# Mainboard_MotorDriverInterface.net
KiCad netlist of a schematic drawn in Altium Designer
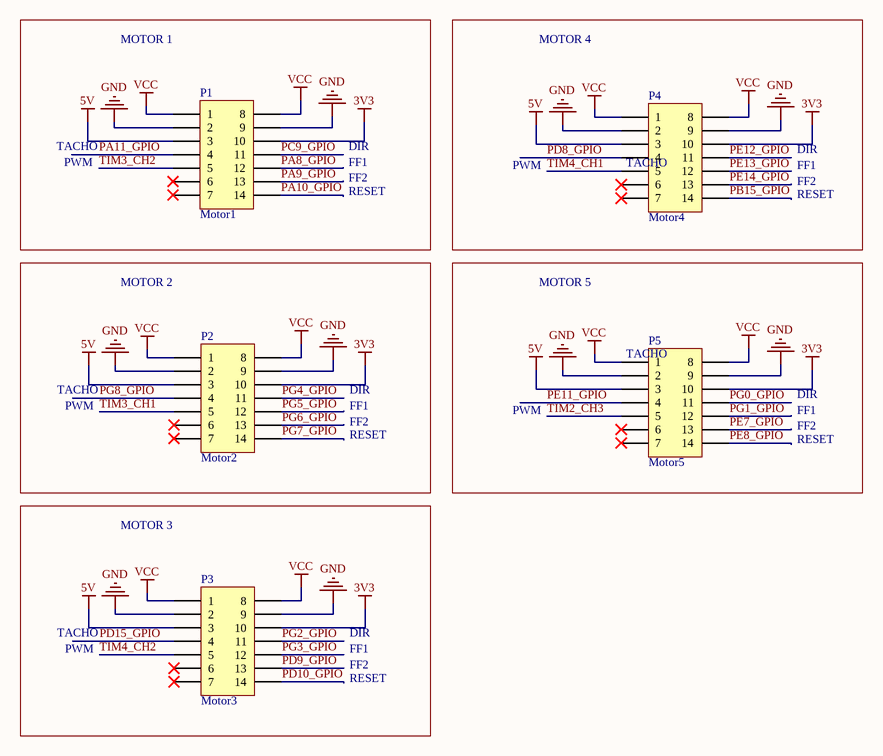
[diagram p0: Mainboard_MotorDriverInterface.SchDoc]

(export (version "E")
  (design (tool "Eeschema 10.0.6"))
  (components
    (comp (ref "P1")
      (value "Motor1")
      (footprint "HDR2X7_CEN")
      (description "Header, 7-Pin, Dual row")
      (fields (field (name "PUBLISHER") "Altium Limited"))
      (libsource (lib "Miscellaneous Connectors") (part "Header 7X2A"))
    )
    (comp (ref "P2")
      (value "Motor2")
      (footprint "HDR2X7_CEN")
      (description "Header, 7-Pin, Dual row")
      (fields (field (name "PUBLISHER") "Altium Limited"))
      (libsource (lib "Miscellaneous Connectors") (part "Header 7X2A"))
    )
    (comp (ref "P3")
      (value "Motor3")
      (footprint "HDR2X7_CEN")
      (description "Header, 7-Pin, Dual row")
      (fields (field (name "PUBLISHER") "Altium Limited"))
      (libsource (lib "Miscellaneous Connectors") (part "Header 7X2A"))
    )
    (comp (ref "P4")
      (value "Motor4")
      (footprint "HDR2X7_CEN")
      (description "Header, 7-Pin, Dual row")
      (fields (field (name "PUBLISHER") "Altium Limited"))
      (libsource (lib "Miscellaneous Connectors") (part "Header 7X2A"))
    )
    (comp (ref "P5")
      (value "Motor5")
      (footprint "HDR2X7_CEN")
      (description "Header, 7-Pin, Dual row")
      (fields (field (name "PUBLISHER") "Altium Limited"))
      (libsource (lib "Miscellaneous Connectors") (part "Header 7X2A"))
    )
  )
  (nets
    (net (code "1") (name "/PA8_GPIO") (class "Default")
      (node (ref "P1") (pin "12") (pinfunction "12_12") (pintype "passive"))
    )
    (net (code "2") (name "/PA9_GPIO") (class "Default")
      (node (ref "P1") (pin "13") (pinfunction "13_13") (pintype "passive"))
    )
    (net (code "3") (name "/PA10_GPIO") (class "Default")
      (node (ref "P1") (pin "14") (pinfunction "14_14") (pintype "passive"))
    )
    (net (code "4") (name "/PA11_GPIO") (class "Default")
      (node (ref "P1") (pin "4") (pinfunction "4_4") (pintype "passive"))
    )
    (net (code "5") (name "/PB15_GPIO") (class "Default")
      (node (ref "P4") (pin "14") (pinfunction "14_14") (pintype "passive"))
    )
    (net (code "6") (name "/PC9_GPIO") (class "Default")
      (node (ref "P1") (pin "11") (pinfunction "11_11") (pintype "passive"))
    )
    (net (code "7") (name "/PD8_GPIO") (class "Default")
      (node (ref "P4") (pin "4") (pinfunction "4_4") (pintype "passive"))
    )
    (net (code "8") (name "/PD9_GPIO") (class "Default")
      (node (ref "P3") (pin "13") (pinfunction "13_13") (pintype "passive"))
    )
    (net (code "9") (name "/PD10_GPIO") (class "Default")
      (node (ref "P3") (pin "14") (pinfunction "14_14") (pintype "passive"))
    )
    (net (code "10") (name "/PD15_GPIO") (class "Default")
      (node (ref "P3") (pin "4") (pinfunction "4_4") (pintype "passive"))
    )
    (net (code "11") (name "/PE7_GPIO") (class "Default")
      (node (ref "P5") (pin "13") (pinfunction "13_13") (pintype "passive"))
    )
    (net (code "12") (name "/PE8_GPIO") (class "Default")
      (node (ref "P5") (pin "14") (pinfunction "14_14") (pintype "passive"))
    )
    (net (code "13") (name "/PE11_GPIO") (class "Default")
      (node (ref "P5") (pin "4") (pinfunction "4_4") (pintype "passive"))
    )
    (net (code "14") (name "/PE12_GPIO") (class "Default")
      (node (ref "P4") (pin "11") (pinfunction "11_11") (pintype "passive"))
    )
    (net (code "15") (name "/PE13_GPIO") (class "Default")
      (node (ref "P4") (pin "12") (pinfunction "12_12") (pintype "passive"))
    )
    (net (code "16") (name "/PE14_GPIO") (class "Default")
      (node (ref "P4") (pin "13") (pinfunction "13_13") (pintype "passive"))
    )
    (net (code "17") (name "/PG0_GPIO") (class "Default")
      (node (ref "P5") (pin "11") (pinfunction "11_11") (pintype "passive"))
    )
    (net (code "18") (name "/PG1_GPIO") (class "Default")
      (node (ref "P5") (pin "12") (pinfunction "12_12") (pintype "passive"))
    )
    (net (code "19") (name "/PG2_GPIO") (class "Default")
      (node (ref "P3") (pin "11") (pinfunction "11_11") (pintype "passive"))
    )
    (net (code "20") (name "/PG3_GPIO") (class "Default")
      (node (ref "P3") (pin "12") (pinfunction "12_12") (pintype "passive"))
    )
    (net (code "21") (name "/PG4_GPIO") (class "Default")
      (node (ref "P2") (pin "11") (pinfunction "11_11") (pintype "passive"))
    )
    (net (code "22") (name "/PG5_GPIO") (class "Default")
      (node (ref "P2") (pin "12") (pinfunction "12_12") (pintype "passive"))
    )
    (net (code "23") (name "/PG6_GPIO") (class "Default")
      (node (ref "P2") (pin "13") (pinfunction "13_13") (pintype "passive"))
    )
    (net (code "24") (name "/PG7_GPIO") (class "Default")
      (node (ref "P2") (pin "14") (pinfunction "14_14") (pintype "passive"))
    )
    (net (code "25") (name "/PG8_GPIO") (class "Default")
      (node (ref "P2") (pin "4") (pinfunction "4_4") (pintype "passive"))
    )
    (net (code "26") (name "/TIM2_CH3") (class "Default")
      (node (ref "P5") (pin "5") (pinfunction "5_5") (pintype "passive"))
    )
    (net (code "27") (name "/TIM3_CH1") (class "Default")
      (node (ref "P2") (pin "5") (pinfunction "5_5") (pintype "passive"))
    )
    (net (code "28") (name "/TIM3_CH2") (class "Default")
      (node (ref "P1") (pin "5") (pinfunction "5_5") (pintype "passive"))
    )
    (net (code "29") (name "/TIM4_CH1") (class "Default")
      (node (ref "P4") (pin "5") (pinfunction "5_5") (pintype "passive"))
    )
    (net (code "30") (name "/TIM4_CH2") (class "Default")
      (node (ref "P3") (pin "5") (pinfunction "5_5") (pintype "passive"))
    )
    (net (code "31") (name "3V3") (class "Default")
      (node (ref "P1") (pin "10") (pinfunction "10_10") (pintype "passive"))
      (node (ref "P2") (pin "10") (pinfunction "10_10") (pintype "passive"))
      (node (ref "P3") (pin "10") (pinfunction "10_10") (pintype "passive"))
      (node (ref "P4") (pin "10") (pinfunction "10_10") (pintype "passive"))
      (node (ref "P5") (pin "10") (pinfunction "10_10") (pintype "passive"))
    )
    (net (code "32") (name "5V") (class "Default")
      (node (ref "P1") (pin "3") (pinfunction "3_3") (pintype "passive"))
      (node (ref "P2") (pin "3") (pinfunction "3_3") (pintype "passive"))
      (node (ref "P3") (pin "3") (pinfunction "3_3") (pintype "passive"))
      (node (ref "P4") (pin "3") (pinfunction "3_3") (pintype "passive"))
      (node (ref "P5") (pin "3") (pinfunction "3_3") (pintype "passive"))
    )
    (net (code "33") (name "GND") (class "Default")
      (node (ref "P1") (pin "2") (pinfunction "2_2") (pintype "passive"))
      (node (ref "P1") (pin "9") (pinfunction "9_9") (pintype "passive"))
      (node (ref "P2") (pin "2") (pinfunction "2_2") (pintype "passive"))
      (node (ref "P2") (pin "9") (pinfunction "9_9") (pintype "passive"))
      (node (ref "P3") (pin "2") (pinfunction "2_2") (pintype "passive"))
      (node (ref "P3") (pin "9") (pinfunction "9_9") (pintype "passive"))
      (node (ref "P4") (pin "2") (pinfunction "2_2") (pintype "passive"))
      (node (ref "P4") (pin "9") (pinfunction "9_9") (pintype "passive"))
      (node (ref "P5") (pin "2") (pinfunction "2_2") (pintype "passive"))
      (node (ref "P5") (pin "9") (pinfunction "9_9") (pintype "passive"))
    )
    (net (code "34") (name "VCC") (class "Default")
      (node (ref "P1") (pin "1") (pinfunction "1_1") (pintype "passive"))
      (node (ref "P1") (pin "8") (pinfunction "8_8") (pintype "passive"))
      (node (ref "P2") (pin "1") (pinfunction "1_1") (pintype "passive"))
      (node (ref "P2") (pin "8") (pinfunction "8_8") (pintype "passive"))
      (node (ref "P3") (pin "1") (pinfunction "1_1") (pintype "passive"))
      (node (ref "P3") (pin "8") (pinfunction "8_8") (pintype "passive"))
      (node (ref "P4") (pin "1") (pinfunction "1_1") (pintype "passive"))
      (node (ref "P4") (pin "8") (pinfunction "8_8") (pintype "passive"))
      (node (ref "P5") (pin "1") (pinfunction "1_1") (pintype "passive"))
      (node (ref "P5") (pin "8") (pinfunction "8_8") (pintype "passive"))
    )
    (net (code "35") (name "unconnected-(P1-Pad6)") (class "Default")
      (node (ref "P1") (pin "6") (pinfunction "6_6") (pintype "passive+no_connect"))
    )
    (net (code "36") (name "unconnected-(P1-Pad7)") (class "Default")
      (node (ref "P1") (pin "7") (pinfunction "7_7") (pintype "passive+no_connect"))
    )
    (net (code "37") (name "unconnected-(P2-Pad6)") (class "Default")
      (node (ref "P2") (pin "6") (pinfunction "6_6") (pintype "passive+no_connect"))
    )
    (net (code "38") (name "unconnected-(P2-Pad7)") (class "Default")
      (node (ref "P2") (pin "7") (pinfunction "7_7") (pintype "passive+no_connect"))
    )
    (net (code "39") (name "unconnected-(P3-Pad6)") (class "Default")
      (node (ref "P3") (pin "6") (pinfunction "6_6") (pintype "passive+no_connect"))
    )
    (net (code "40") (name "unconnected-(P3-Pad7)") (class "Default")
      (node (ref "P3") (pin "7") (pinfunction "7_7") (pintype "passive+no_connect"))
    )
    (net (code "41") (name "unconnected-(P4-Pad6)") (class "Default")
      (node (ref "P4") (pin "6") (pinfunction "6_6") (pintype "passive+no_connect"))
    )
    (net (code "42") (name "unconnected-(P4-Pad7)") (class "Default")
      (node (ref "P4") (pin "7") (pinfunction "7_7") (pintype "passive+no_connect"))
    )
    (net (code "43") (name "unconnected-(P5-Pad6)") (class "Default")
      (node (ref "P5") (pin "6") (pinfunction "6_6") (pintype "passive+no_connect"))
    )
    (net (code "44") (name "unconnected-(P5-Pad7)") (class "Default")
      (node (ref "P5") (pin "7") (pinfunction "7_7") (pintype "passive+no_connect"))
    )
  )
)
